# picoschem.net
KiCad netlist of a schematic drawn in EasyEDA
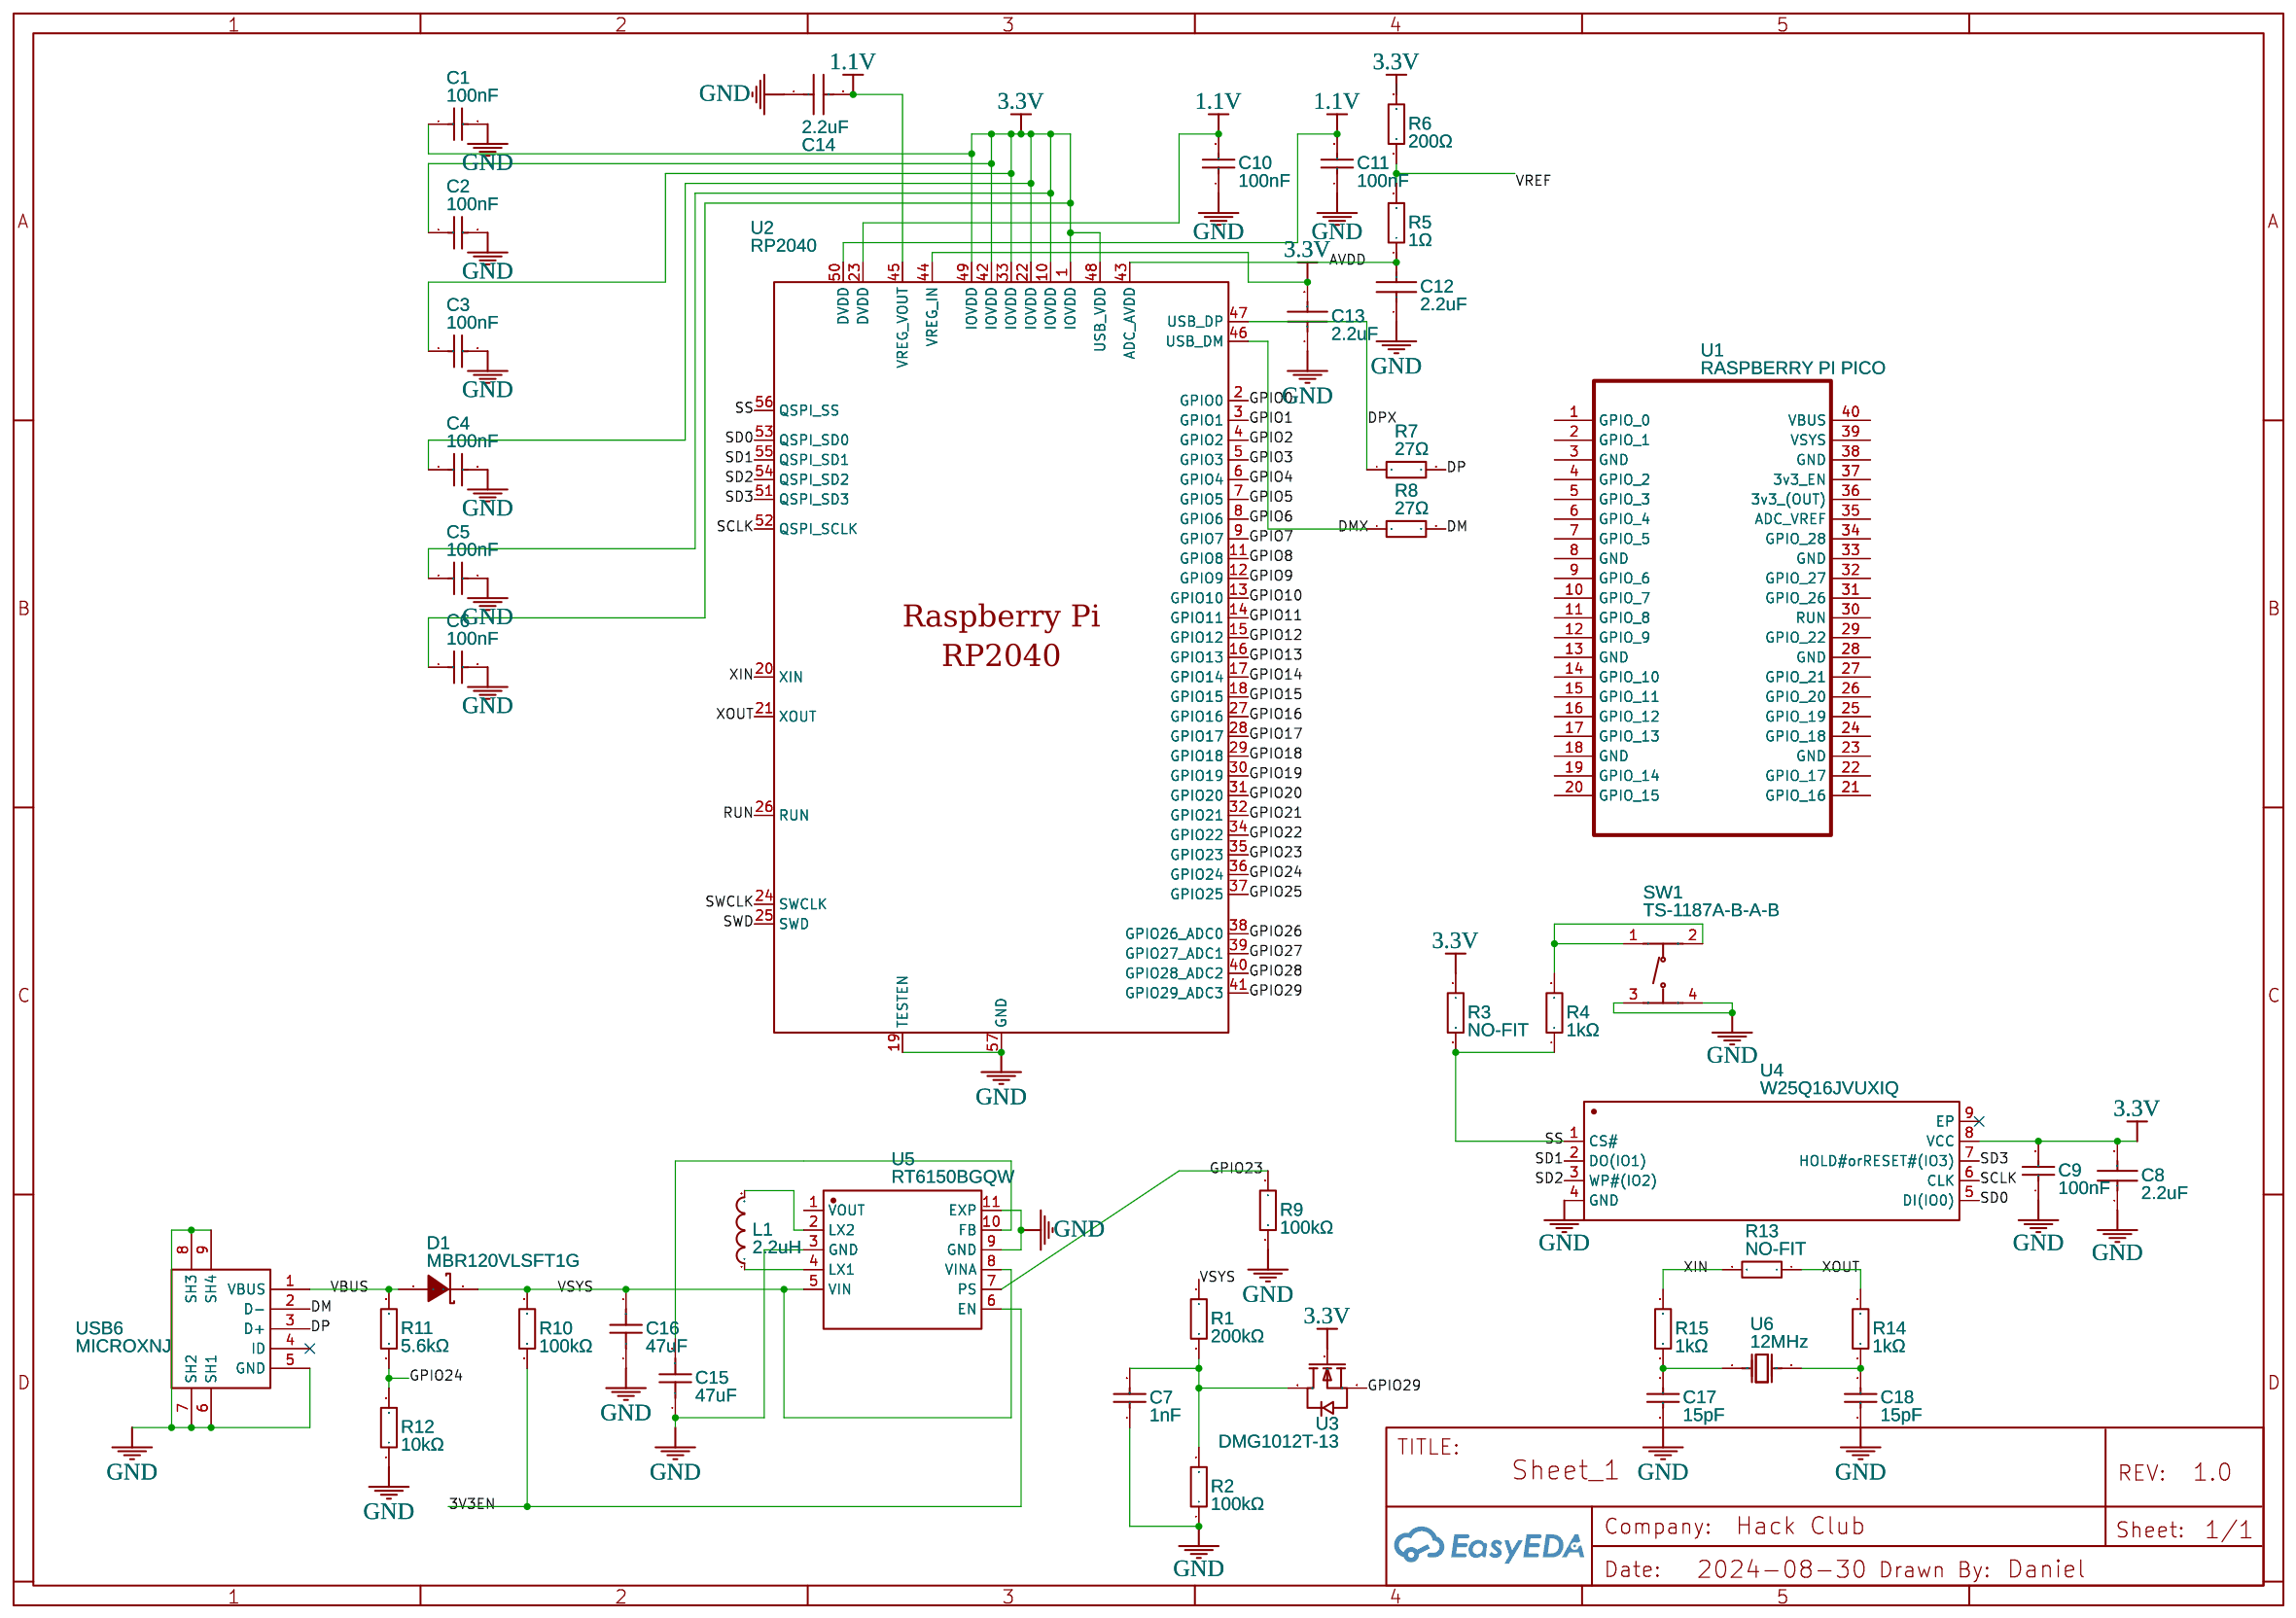
[diagram p0: schematic sheet]

(export (version "E")
  (design (tool "Eeschema 10.0.6"))
  (components
    (comp (ref "C1")
      (value "100nF")
      (fields (field (name "Manufacturer Part") "CGA3E2X7R1H104KT0Y0N") (field (name "Manufacturer") "TDK"))
      (libsource (lib "") (part "CGA3E2X7R1H104KT0Y0N_1"))
    )
    (comp (ref "C2")
      (value "100nF")
      (fields (field (name "Manufacturer Part") "CGA3E2X7R1H104KT0Y0N") (field (name "Manufacturer") "TDK"))
      (libsource (lib "") (part "CGA3E2X7R1H104KT0Y0N_1"))
    )
    (comp (ref "C3")
      (value "100nF")
      (fields (field (name "Manufacturer Part") "CGA3E2X7R1H104KT0Y0N") (field (name "Manufacturer") "TDK"))
      (libsource (lib "") (part "CGA3E2X7R1H104KT0Y0N_1"))
    )
    (comp (ref "C4")
      (value "100nF")
      (fields (field (name "Manufacturer Part") "CGA3E2X7R1H104KT0Y0N") (field (name "Manufacturer") "TDK"))
      (libsource (lib "") (part "CGA3E2X7R1H104KT0Y0N_1"))
    )
    (comp (ref "C5")
      (value "100nF")
      (fields (field (name "Manufacturer Part") "CGA3E2X7R1H104KT0Y0N") (field (name "Manufacturer") "TDK"))
      (libsource (lib "") (part "CGA3E2X7R1H104KT0Y0N_1"))
    )
    (comp (ref "C6")
      (value "100nF")
      (fields (field (name "Manufacturer Part") "CGA3E2X7R1H104KT0Y0N") (field (name "Manufacturer") "TDK"))
      (libsource (lib "") (part "CGA3E2X7R1H104KT0Y0N_1"))
    )
    (comp (ref "C7")
      (value "1nF")
      (fields (field (name "Manufacturer Part") "0805CG102J500NT") (field (name "Manufacturer") "FH(风华)"))
      (libsource (lib "") (part "0805CG102J500NT"))
    )
    (comp (ref "C8")
      (value "2.2uF")
      (fields
        (field (name "Manufacturer Part") "CL05A225MQ5NSNC")
        (field (name "Manufacturer") "SAMSUNG(三星)")
      )
      (libsource (lib "") (part "CL05A225MQ5NSNC_1"))
    )
    (comp (ref "C9")
      (value "100nF")
      (fields (field (name "Manufacturer Part") "CGA3E2X7R1H104KT0Y0N") (field (name "Manufacturer") "TDK"))
      (libsource (lib "") (part "CGA3E2X7R1H104KT0Y0N"))
    )
    (comp (ref "C10")
      (value "100nF")
      (fields (field (name "Manufacturer Part") "CGA3E2X7R1H104KT0Y0N") (field (name "Manufacturer") "TDK"))
      (libsource (lib "") (part "CGA3E2X7R1H104KT0Y0N"))
    )
    (comp (ref "C11")
      (value "100nF")
      (fields (field (name "Manufacturer Part") "CGA3E2X7R1H104KT0Y0N") (field (name "Manufacturer") "TDK"))
      (libsource (lib "") (part "CGA3E2X7R1H104KT0Y0N"))
    )
    (comp (ref "C12")
      (value "2.2uF")
      (fields
        (field (name "Manufacturer Part") "CL05A225MQ5NSNC")
        (field (name "Manufacturer") "SAMSUNG(三星)")
      )
      (libsource (lib "") (part "CL05A225MQ5NSNC_1"))
    )
    (comp (ref "C13")
      (value "2.2uF")
      (fields
        (field (name "Manufacturer Part") "CL05A225MQ5NSNC")
        (field (name "Manufacturer") "SAMSUNG(三星)")
      )
      (libsource (lib "") (part "CL05A225MQ5NSNC_1"))
    )
    (comp (ref "C14")
      (value "2.2uF")
      (fields
        (field (name "Manufacturer Part") "CL05A225MQ5NSNC")
        (field (name "Manufacturer") "SAMSUNG(三星)")
      )
      (libsource (lib "") (part "CL05A225MQ5NSNC"))
    )
    (comp (ref "C15")
      (value "47uF")
      (fields
        (field (name "Manufacturer Part") "CGA0805X5R476M100MT")
        (field (name "Manufacturer") "HRE(芯声)")
      )
      (libsource (lib "") (part "CGA0805X5R476M100MT"))
    )
    (comp (ref "C16")
      (value "47uF")
      (fields
        (field (name "Manufacturer Part") "CGA0805X5R476M100MT")
        (field (name "Manufacturer") "HRE(芯声)")
      )
      (libsource (lib "") (part "CGA0805X5R476M100MT"))
    )
    (comp (ref "C17")
      (value "15pF")
      (fields
        (field (name "Manufacturer Part") "CC0402JRNPO9BN150")
        (field (name "Manufacturer") "YAGEO(国巨)")
      )
      (libsource (lib "") (part "CC0402JRNPO9BN150"))
    )
    (comp (ref "C18")
      (value "15pF")
      (fields
        (field (name "Manufacturer Part") "CC0402JRNPO9BN150")
        (field (name "Manufacturer") "YAGEO(国巨)")
      )
      (libsource (lib "") (part "CC0402JRNPO9BN150"))
    )
    (comp (ref "D1")
      (value "MBR120VLSFT1G")
      (fields (field (name "Manufacturer") "onsemi(安森美)"))
      (libsource (lib "") (part "MBR120VLSFT1G"))
    )
    (comp (ref "L1")
      (value "2.2uH")
      (fields (field (name "Manufacturer Part") "CMI201209U2R2KT") (field (name "Manufacturer") "FH(风华)"))
      (libsource (lib "") (part "CMI201209U2R2KT"))
    )
    (comp (ref "R1")
      (value "200kΩ")
      (fields
        (field (name "Manufacturer Part") "0603WAF2003T5E")
        (field (name "Manufacturer") "UNI-ROYAL(厚声)")
      )
      (libsource (lib "") (part "0603WAF2003T5E"))
    )
    (comp (ref "R2")
      (value "100kΩ")
      (fields
        (field (name "Manufacturer Part") "0603WAF1003T5E")
        (field (name "Manufacturer") "UNI-ROYAL(厚声)")
      )
      (libsource (lib "") (part "0603WAF1003T5E"))
    )
    (comp (ref "R3")
      (value "NO-FIT")
      (fields
        (field (name "Manufacturer Part") "0603WAF2003T5E")
        (field (name "Manufacturer") "UNI-ROYAL(厚声)")
      )
      (libsource (lib "") (part "0603WAF2003T5E"))
    )
    (comp (ref "R4")
      (value "1kΩ")
      (fields
        (field (name "Manufacturer Part") "0603WAF1001T5E")
        (field (name "Manufacturer") "UNI-ROYAL(厚声)")
      )
      (libsource (lib "") (part "0603WAF1001T5E_1"))
    )
    (comp (ref "R5")
      (value "1Ω")
      (fields
        (field (name "Manufacturer Part") "0805W8F100KT5E")
        (field (name "Manufacturer") "UNI-ROYAL(厚声)")
      )
      (libsource (lib "") (part "0805W8F100KT5E"))
    )
    (comp (ref "R6")
      (value "200Ω")
      (fields
        (field (name "Manufacturer Part") "0603WAF2000T5E")
        (field (name "Manufacturer") "UNI-ROYAL(厚声)")
      )
      (libsource (lib "") (part "0603WAF2000T5E"))
    )
    (comp (ref "R7")
      (value "27Ω")
      (fields
        (field (name "Manufacturer Part") "0603WAF270JT5E")
        (field (name "Manufacturer") "UNI-ROYAL(厚声)")
      )
      (libsource (lib "") (part "0603WAF270JT5E"))
    )
    (comp (ref "R8")
      (value "27Ω")
      (fields
        (field (name "Manufacturer Part") "0603WAF270JT5E")
        (field (name "Manufacturer") "UNI-ROYAL(厚声)")
      )
      (libsource (lib "") (part "0603WAF270JT5E"))
    )
    (comp (ref "R9")
      (value "100kΩ")
      (fields
        (field (name "Manufacturer Part") "0603WAF1003T5E")
        (field (name "Manufacturer") "UNI-ROYAL(厚声)")
      )
      (libsource (lib "") (part "0603WAF1003T5E"))
    )
    (comp (ref "R10")
      (value "100kΩ")
      (fields
        (field (name "Manufacturer Part") "0603WAF1003T5E")
        (field (name "Manufacturer") "UNI-ROYAL(厚声)")
      )
      (libsource (lib "") (part "0603WAF1003T5E"))
    )
    (comp (ref "R11")
      (value "5.6kΩ")
      (fields (field (name "Manufacturer Part") "RM10FTN5601") (field (name "Manufacturer") "大毅科技"))
      (libsource (lib "") (part "RM10FTN5601"))
    )
    (comp (ref "R12")
      (value "10kΩ")
      (fields
        (field (name "Manufacturer Part") "0603WAF1002T5E")
        (field (name "Manufacturer") "UNI-ROYAL(厚声)")
      )
      (libsource (lib "") (part "0603WAF1002T5E"))
    )
    (comp (ref "R13")
      (value "NO-FIT")
      (fields
        (field (name "Manufacturer Part") "0603WAF1001T5E")
        (field (name "Manufacturer") "UNI-ROYAL(厚声)")
      )
      (libsource (lib "") (part "0603WAF1001T5E"))
    )
    (comp (ref "R14")
      (value "1kΩ")
      (fields
        (field (name "Manufacturer Part") "0603WAF1001T5E")
        (field (name "Manufacturer") "UNI-ROYAL(厚声)")
      )
      (libsource (lib "") (part "0603WAF1001T5E_1"))
    )
    (comp (ref "R15")
      (value "1kΩ")
      (fields
        (field (name "Manufacturer Part") "0603WAF1001T5E")
        (field (name "Manufacturer") "UNI-ROYAL(厚声)")
      )
      (libsource (lib "") (part "0603WAF1001T5E_1"))
    )
    (comp (ref "SW1")
      (value "TS-1187A-B-A-B")
      (fields (field (name "Manufacturer") "XKB Connectivity(中国星坤)"))
      (libsource (lib "") (part "TS-1187A-B-A-B"))
    )
    (comp (ref "U1") (value "RASPBERRY PI PICO") (libsource (lib "") (part "RASPBERRY PI PICO")))
    (comp (ref "U2")
      (value "RP2040")
      (fields (field (name "Manufacturer") "Raspberry Pi(树莓派)"))
      (libsource (lib "") (part "RP2040"))
    )
    (comp (ref "U3")
      (value "DMG1012T-13")
      (fields (field (name "Manufacturer") "DIODES(美台)"))
      (libsource (lib "") (part "DMG1012T-13"))
    )
    (comp (ref "U4")
      (value "W25Q16JVUXIQ")
      (fields (field (name "Manufacturer") "WINBOND(华邦)"))
      (libsource (lib "") (part "W25Q16JVUXIQ"))
    )
    (comp (ref "U5")
      (value "RT6150BGQW")
      (fields (field (name "Manufacturer") "RICHTEK(立锜)"))
      (libsource (lib "") (part "RT6150BGQW"))
    )
    (comp (ref "U6")
      (value "12MHz")
      (fields
        (field (name "Manufacturer Part") "ABLS-12.000MHZ-B4-T")
        (field (name "Manufacturer") "ABRACON")
      )
      (libsource (lib "") (part "ABLS-12.000MHZ-B4-T"))
    )
    (comp (ref "USB6")
      (value "MICROXNJ")
      (fields (field (name "Manufacturer Part") "MicroXNJ") (field (name "Manufacturer") "SHOU HAN(首韩)"))
      (libsource (lib "") (part "MICROXNJ"))
    )
  )
  (nets
    (net (code "1") (name "/3V3EN") (class "Default")
      (node (ref "R10") (pin "1") (pinfunction "1_1") (pintype "input"))
      (node (ref "U5") (pin "6") (pinfunction "EN_6") (pintype "unspecified"))
    )
    (net (code "2") (name "/AVDD") (class "Default")
      (node (ref "C12") (pin "2") (pinfunction "2_2") (pintype "unspecified"))
      (node (ref "R5") (pin "1") (pinfunction "1_1") (pintype "input"))
      (node (ref "U2") (pin "43") (pinfunction "ADC_AVDD_43") (pintype "bidirectional"))
    )
    (net (code "3") (name "/DM") (class "Default")
      (node (ref "R8") (pin "2") (pinfunction "2_2") (pintype "input"))
      (node (ref "USB6") (pin "2") (pinfunction "D-_2") (pintype "unspecified"))
    )
    (net (code "4") (name "/DMX") (class "Default")
      (node (ref "R8") (pin "1") (pinfunction "1_1") (pintype "input"))
      (node (ref "U2") (pin "46") (pinfunction "USB_DM_46") (pintype "bidirectional"))
    )
    (net (code "5") (name "/DP") (class "Default")
      (node (ref "R7") (pin "2") (pinfunction "2_2") (pintype "input"))
      (node (ref "USB6") (pin "3") (pinfunction "D+_3") (pintype "unspecified"))
    )
    (net (code "6") (name "/DPX") (class "Default")
      (node (ref "R7") (pin "1") (pinfunction "1_1") (pintype "input"))
      (node (ref "U2") (pin "47") (pinfunction "USB_DP_47") (pintype "bidirectional"))
    )
    (net (code "7") (name "/GPIO0") (class "Default")
      (node (ref "U2") (pin "2") (pinfunction "GPIO0_2") (pintype "bidirectional"))
    )
    (net (code "8") (name "/GPIO1") (class "Default")
      (node (ref "U2") (pin "3") (pinfunction "GPIO1_3") (pintype "bidirectional"))
    )
    (net (code "9") (name "/GPIO2") (class "Default")
      (node (ref "U2") (pin "4") (pinfunction "GPIO2_4") (pintype "bidirectional"))
    )
    (net (code "10") (name "/GPIO3") (class "Default")
      (node (ref "U2") (pin "5") (pinfunction "GPIO3_5") (pintype "bidirectional"))
    )
    (net (code "11") (name "/GPIO4") (class "Default")
      (node (ref "U2") (pin "6") (pinfunction "GPIO4_6") (pintype "bidirectional"))
    )
    (net (code "12") (name "/GPIO5") (class "Default")
      (node (ref "U2") (pin "7") (pinfunction "GPIO5_7") (pintype "bidirectional"))
    )
    (net (code "13") (name "/GPIO6") (class "Default")
      (node (ref "U2") (pin "8") (pinfunction "GPIO6_8") (pintype "bidirectional"))
    )
    (net (code "14") (name "/GPIO7") (class "Default")
      (node (ref "U2") (pin "9") (pinfunction "GPIO7_9") (pintype "bidirectional"))
    )
    (net (code "15") (name "/GPIO8") (class "Default")
      (node (ref "U2") (pin "11") (pinfunction "GPIO8_11") (pintype "bidirectional"))
    )
    (net (code "16") (name "/GPIO9") (class "Default")
      (node (ref "U2") (pin "12") (pinfunction "GPIO9_12") (pintype "bidirectional"))
    )
    (net (code "17") (name "/GPIO10") (class "Default")
      (node (ref "U2") (pin "13") (pinfunction "GPIO10_13") (pintype "bidirectional"))
    )
    (net (code "18") (name "/GPIO11") (class "Default")
      (node (ref "U2") (pin "14") (pinfunction "GPIO11_14") (pintype "bidirectional"))
    )
    (net (code "19") (name "/GPIO12") (class "Default")
      (node (ref "U2") (pin "15") (pinfunction "GPIO12_15") (pintype "bidirectional"))
    )
    (net (code "20") (name "/GPIO13") (class "Default")
      (node (ref "U2") (pin "16") (pinfunction "GPIO13_16") (pintype "bidirectional"))
    )
    (net (code "21") (name "/GPIO14") (class "Default")
      (node (ref "U2") (pin "17") (pinfunction "GPIO14_17") (pintype "bidirectional"))
    )
    (net (code "22") (name "/GPIO15") (class "Default")
      (node (ref "U2") (pin "18") (pinfunction "GPIO15_18") (pintype "bidirectional"))
    )
    (net (code "23") (name "/GPIO16") (class "Default")
      (node (ref "U2") (pin "27") (pinfunction "GPIO16_27") (pintype "bidirectional"))
    )
    (net (code "24") (name "/GPIO17") (class "Default")
      (node (ref "U2") (pin "28") (pinfunction "GPIO17_28") (pintype "bidirectional"))
    )
    (net (code "25") (name "/GPIO18") (class "Default")
      (node (ref "U2") (pin "29") (pinfunction "GPIO18_29") (pintype "bidirectional"))
    )
    (net (code "26") (name "/GPIO19") (class "Default")
      (node (ref "U2") (pin "30") (pinfunction "GPIO19_30") (pintype "bidirectional"))
    )
    (net (code "27") (name "/GPIO20") (class "Default")
      (node (ref "U2") (pin "31") (pinfunction "GPIO20_31") (pintype "bidirectional"))
    )
    (net (code "28") (name "/GPIO21") (class "Default")
      (node (ref "U2") (pin "32") (pinfunction "GPIO21_32") (pintype "bidirectional"))
    )
    (net (code "29") (name "/GPIO22") (class "Default")
      (node (ref "U2") (pin "34") (pinfunction "GPIO22_34") (pintype "bidirectional"))
    )
    (net (code "30") (name "/GPIO23") (class "Default")
      (node (ref "R9") (pin "2") (pinfunction "2_2") (pintype "input"))
      (node (ref "U2") (pin "35") (pinfunction "GPIO23_35") (pintype "bidirectional"))
      (node (ref "U5") (pin "7") (pinfunction "PS_7") (pintype "unspecified"))
    )
    (net (code "31") (name "/GPIO24") (class "Default")
      (node (ref "R11") (pin "1") (pinfunction "1_1") (pintype "unspecified"))
      (node (ref "R12") (pin "2") (pinfunction "2_2") (pintype "input"))
      (node (ref "U2") (pin "36") (pinfunction "GPIO24_36") (pintype "bidirectional"))
    )
    (net (code "32") (name "/GPIO25") (class "Default")
      (node (ref "U2") (pin "37") (pinfunction "GPIO25_37") (pintype "bidirectional"))
    )
    (net (code "33") (name "/GPIO26") (class "Default")
      (node (ref "U2") (pin "38") (pinfunction "GPIO26_ADC0_38") (pintype "bidirectional"))
    )
    (net (code "34") (name "/GPIO27") (class "Default")
      (node (ref "U2") (pin "39") (pinfunction "GPIO27_ADC1_39") (pintype "bidirectional"))
    )
    (net (code "35") (name "/GPIO28") (class "Default")
      (node (ref "U2") (pin "40") (pinfunction "GPIO28_ADC2_40") (pintype "bidirectional"))
    )
    (net (code "36") (name "/GPIO29") (class "Default")
      (node (ref "U2") (pin "41") (pinfunction "GPIO29_ADC3_41") (pintype "bidirectional"))
      (node (ref "U3") (pin "2") (pinfunction "S_2") (pintype "unspecified"))
    )
    (net (code "37") (name "/RUN") (class "Default")
      (node (ref "U2") (pin "26") (pinfunction "RUN_26") (pintype "input"))
    )
    (net (code "38") (name "/SCLK") (class "Default")
      (node (ref "U2") (pin "52") (pinfunction "QSPI_SCLK_52") (pintype "output"))
      (node (ref "U4") (pin "6") (pinfunction "CLK_6") (pintype "unspecified"))
    )
    (net (code "39") (name "/SD0") (class "Default")
      (node (ref "U2") (pin "53") (pinfunction "QSPI_SD0_53") (pintype "bidirectional"))
      (node (ref "U4") (pin "5") (pinfunction "DI(IO0)_5") (pintype "unspecified"))
    )
    (net (code "40") (name "/SD1") (class "Default")
      (node (ref "U2") (pin "55") (pinfunction "QSPI_SD1_55") (pintype "bidirectional"))
      (node (ref "U4") (pin "2") (pinfunction "DO(IO1)_2") (pintype "unspecified"))
    )
    (net (code "41") (name "/SD2") (class "Default")
      (node (ref "U2") (pin "54") (pinfunction "QSPI_SD2_54") (pintype "bidirectional"))
      (node (ref "U4") (pin "3") (pinfunction "WP#(IO2)_3") (pintype "unspecified"))
    )
    (net (code "42") (name "/SD3") (class "Default")
      (node (ref "U2") (pin "51") (pinfunction "QSPI_SD3_51") (pintype "bidirectional"))
      (node (ref "U4") (pin "7") (pinfunction "HOLD#orRESET#(IO3)_7") (pintype "unspecified"))
    )
    (net (code "43") (name "/SS") (class "Default")
      (node (ref "R3") (pin "2") (pinfunction "2_2") (pintype "input"))
      (node (ref "R4") (pin "1") (pinfunction "1_1") (pintype "input"))
      (node (ref "U2") (pin "56") (pinfunction "QSPI_SS_56") (pintype "bidirectional"))
      (node (ref "U4") (pin "1") (pinfunction "CS#_1") (pintype "unspecified"))
    )
    (net (code "44") (name "/SWCLK") (class "Default")
      (node (ref "U2") (pin "24") (pinfunction "SWCLK_24") (pintype "output"))
    )
    (net (code "45") (name "/SWD") (class "Default")
      (node (ref "U2") (pin "25") (pinfunction "SWD_25") (pintype "bidirectional"))
    )
    (net (code "46") (name "/VBUS") (class "Default")
      (node (ref "D1") (pin "2") (pinfunction "A_2") (pintype "unspecified"))
      (node (ref "R11") (pin "2") (pinfunction "2_2") (pintype "unspecified"))
      (node (ref "USB6") (pin "1") (pinfunction "VBUS_1") (pintype "unspecified"))
    )
    (net (code "48") (name "/VSYS") (class "Default")
      (node (ref "C16") (pin "2") (pinfunction "2_2") (pintype "unspecified"))
      (node (ref "D1") (pin "1") (pinfunction "K_1") (pintype "unspecified"))
      (node (ref "R1") (pin "1") (pinfunction "1_1") (pintype "input"))
      (node (ref "R10") (pin "2") (pinfunction "2_2") (pintype "input"))
      (node (ref "U5") (pin "5") (pinfunction "VIN_5") (pintype "unspecified"))
      (node (ref "U5") (pin "8") (pinfunction "VINA_8") (pintype "unspecified"))
    )
    (net (code "49") (name "/XIN") (class "Default")
      (node (ref "R13") (pin "2") (pinfunction "2_2") (pintype "input"))
      (node (ref "R15") (pin "2") (pinfunction "2_2") (pintype "input"))
      (node (ref "U2") (pin "20") (pinfunction "XIN_20") (pintype "input"))
    )
    (net (code "50") (name "/XOUT") (class "Default")
      (node (ref "R13") (pin "1") (pinfunction "1_1") (pintype "input"))
      (node (ref "R14") (pin "2") (pinfunction "2_2") (pintype "input"))
      (node (ref "U2") (pin "21") (pinfunction "XOUT_21") (pintype "unspecified"))
    )
    (net (code "51") (name "1.1V") (class "Default")
      (node (ref "C10") (pin "2") (pinfunction "2_2") (pintype "input"))
      (node (ref "C11") (pin "2") (pinfunction "2_2") (pintype "input"))
      (node (ref "C14") (pin "2") (pinfunction "2_2") (pintype "unspecified"))
      (node (ref "U2") (pin "23") (pinfunction "DVDD_23") (pintype "bidirectional"))
      (node (ref "U2") (pin "45") (pinfunction "VREG_VOUT_45") (pintype "bidirectional"))
      (node (ref "U2") (pin "50") (pinfunction "DVDD_50") (pintype "bidirectional"))
    )
    (net (code "52") (name "3.3V") (class "Default")
      (node (ref "C1") (pin "1") (pinfunction "1_1") (pintype "input"))
      (node (ref "C13") (pin "2") (pinfunction "2_2") (pintype "unspecified"))
      (node (ref "C2") (pin "1") (pinfunction "1_1") (pintype "input"))
      (node (ref "C3") (pin "1") (pinfunction "1_1") (pintype "input"))
      (node (ref "C4") (pin "1") (pinfunction "1_1") (pintype "input"))
      (node (ref "C5") (pin "1") (pinfunction "1_1") (pintype "input"))
      (node (ref "C6") (pin "1") (pinfunction "1_1") (pintype "input"))
      (node (ref "C8") (pin "2") (pinfunction "2_2") (pintype "unspecified"))
      (node (ref "C9") (pin "2") (pinfunction "2_2") (pintype "input"))
      (node (ref "R3") (pin "1") (pinfunction "1_1") (pintype "input"))
      (node (ref "R6") (pin "2") (pinfunction "2_2") (pintype "input"))
      (node (ref "U2") (pin "1") (pinfunction "IOVDD_1") (pintype "bidirectional"))
      (node (ref "U2") (pin "10") (pinfunction "IOVDD_10") (pintype "bidirectional"))
      (node (ref "U2") (pin "22") (pinfunction "IOVDD_22") (pintype "bidirectional"))
      (node (ref "U2") (pin "33") (pinfunction "IOVDD_33") (pintype "bidirectional"))
      (node (ref "U2") (pin "42") (pinfunction "IOVDD_42") (pintype "bidirectional"))
      (node (ref "U2") (pin "44") (pinfunction "VREG_IN_44") (pintype "bidirectional"))
      (node (ref "U2") (pin "48") (pinfunction "USB_VDD_48") (pintype "bidirectional"))
      (node (ref "U2") (pin "49") (pinfunction "IOVDD_49") (pintype "bidirectional"))
      (node (ref "U3") (pin "1") (pinfunction "G_1") (pintype "unspecified"))
      (node (ref "U4") (pin "8") (pinfunction "VCC_8") (pintype "unspecified"))
    )
    (net (code "53") (name "GND") (class "Default")
      (node (ref "C1") (pin "2") (pinfunction "2_2") (pintype "input"))
      (node (ref "C10") (pin "1") (pinfunction "1_1") (pintype "input"))
      (node (ref "C11") (pin "1") (pinfunction "1_1") (pintype "input"))
      (node (ref "C12") (pin "1") (pinfunction "1_1") (pintype "unspecified"))
      (node (ref "C13") (pin "1") (pinfunction "1_1") (pintype "unspecified"))
      (node (ref "C14") (pin "1") (pinfunction "1_1") (pintype "unspecified"))
      (node (ref "C15") (pin "1") (pinfunction "1_1") (pintype "unspecified"))
      (node (ref "C16") (pin "1") (pinfunction "1_1") (pintype "unspecified"))
      (node (ref "C17") (pin "1") (pinfunction "1_1") (pintype "input"))
      (node (ref "C18") (pin "1") (pinfunction "1_1") (pintype "input"))
      (node (ref "C2") (pin "2") (pinfunction "2_2") (pintype "input"))
      (node (ref "C3") (pin "2") (pinfunction "2_2") (pintype "input"))
      (node (ref "C4") (pin "2") (pinfunction "2_2") (pintype "input"))
      (node (ref "C5") (pin "2") (pinfunction "2_2") (pintype "input"))
      (node (ref "C6") (pin "2") (pinfunction "2_2") (pintype "input"))
      (node (ref "C7") (pin "1") (pinfunction "1_1") (pintype "input"))
      (node (ref "C8") (pin "1") (pinfunction "1_1") (pintype "unspecified"))
      (node (ref "C9") (pin "1") (pinfunction "1_1") (pintype "input"))
      (node (ref "R12") (pin "1") (pinfunction "1_1") (pintype "input"))
      (node (ref "R2") (pin "1") (pinfunction "1_1") (pintype "input"))
      (node (ref "R9") (pin "1") (pinfunction "1_1") (pintype "input"))
      (node (ref "SW1") (pin "3") (pinfunction "C_3") (pintype "unspecified"))
      (node (ref "SW1") (pin "4") (pinfunction "D_4") (pintype "unspecified"))
      (node (ref "U2") (pin "19") (pinfunction "TESTEN_19") (pintype "unspecified"))
      (node (ref "U2") (pin "57") (pinfunction "GND_57") (pintype "bidirectional"))
      (node (ref "U4") (pin "4") (pinfunction "GND_4") (pintype "unspecified"))
      (node (ref "U5") (pin "11") (pinfunction "EXP_11") (pintype "unspecified"))
      (node (ref "U5") (pin "3") (pinfunction "GND_3") (pintype "unspecified"))
      (node (ref "U5") (pin "9") (pinfunction "GND_9") (pintype "unspecified"))
      (node (ref "USB6") (pin "5") (pinfunction "GND_5") (pintype "unspecified"))
      (node (ref "USB6") (pin "6") (pinfunction "SH1_6") (pintype "unspecified"))
      (node (ref "USB6") (pin "7") (pinfunction "SH2_7") (pintype "unspecified"))
      (node (ref "USB6") (pin "8") (pinfunction "SH3_8") (pintype "unspecified"))
      (node (ref "USB6") (pin "9") (pinfunction "SH4_9") (pintype "unspecified"))
    )
    (net (code "54") (name "Net-(R5-Pad2)") (class "Default")
      (node (ref "R5") (pin "2") (pinfunction "2_2") (pintype "input"))
      (node (ref "R6") (pin "1") (pinfunction "1_1") (pintype "input"))
    )
    (net (code "55") (name "Net-(SW1-A)") (class "Default")
      (node (ref "R4") (pin "2") (pinfunction "2_2") (pintype "input"))
      (node (ref "SW1") (pin "1") (pinfunction "A_1") (pintype "unspecified"))
      (node (ref "SW1") (pin "2") (pinfunction "B_2") (pintype "unspecified"))
    )
    (net (code "56") (name "Net-(U3-D)") (class "Default")
      (node (ref "C7") (pin "2") (pinfunction "2_2") (pintype "input"))
      (node (ref "R1") (pin "2") (pinfunction "2_2") (pintype "input"))
      (node (ref "R2") (pin "2") (pinfunction "2_2") (pintype "input"))
      (node (ref "U3") (pin "3") (pinfunction "D_3") (pintype "unspecified"))
    )
    (net (code "57") (name "Net-(U5-FB)") (class "Default")
      (node (ref "C15") (pin "2") (pinfunction "2_2") (pintype "unspecified"))
      (node (ref "U5") (pin "10") (pinfunction "FB_10") (pintype "unspecified"))
    )
    (net (code "58") (name "Net-(U5-LX1)") (class "Default")
      (node (ref "L1") (pin "1") (pinfunction "1_1") (pintype "unspecified"))
      (node (ref "U5") (pin "4") (pinfunction "LX1_4") (pintype "unspecified"))
    )
    (net (code "59") (name "Net-(U5-LX2)") (class "Default")
      (node (ref "L1") (pin "2") (pinfunction "2_2") (pintype "unspecified"))
      (node (ref "U5") (pin "2") (pinfunction "LX2_2") (pintype "unspecified"))
    )
    (net (code "60") (name "Net-(U6-OSC1)") (class "Default")
      (node (ref "C17") (pin "2") (pinfunction "2_2") (pintype "input"))
      (node (ref "R15") (pin "1") (pinfunction "1_1") (pintype "input"))
      (node (ref "U6") (pin "1") (pinfunction "OSC1_1") (pintype "input"))
    )
    (net (code "61") (name "Net-(U6-OSC2)") (class "Default")
      (node (ref "C18") (pin "2") (pinfunction "2_2") (pintype "input"))
      (node (ref "R14") (pin "1") (pinfunction "1_1") (pintype "input"))
      (node (ref "U6") (pin "2") (pinfunction "OSC2_2") (pintype "input"))
    )
    (net (code "62") (name "unconnected-(U1-3v3_(OUT)-Pad36)") (class "Default")
      (node (ref "U1") (pin "36") (pinfunction "3v3_(OUT)_36") (pintype "unspecified"))
    )
    (net (code "63") (name "unconnected-(U1-3v3_EN-Pad37)") (class "Default")
      (node (ref "U1") (pin "37") (pinfunction "3v3_EN_37") (pintype "unspecified"))
    )
    (net (code "64") (name "unconnected-(U1-ADC_VREF-Pad35)") (class "Default")
      (node (ref "U1") (pin "35") (pinfunction "ADC_VREF_35") (pintype "unspecified"))
    )
    (net (code "65") (name "unconnected-(U1-GND-Pad3)") (class "Default")
      (node (ref "U1") (pin "3") (pinfunction "GND_3") (pintype "unspecified"))
    )
    (net (code "66") (name "unconnected-(U1-GND-Pad8)") (class "Default")
      (node (ref "U1") (pin "8") (pinfunction "GND_8") (pintype "unspecified"))
    )
    (net (code "67") (name "unconnected-(U1-GND-Pad13)") (class "Default")
      (node (ref "U1") (pin "13") (pinfunction "GND_13") (pintype "unspecified"))
    )
    (net (code "68") (name "unconnected-(U1-GND-Pad18)") (class "Default")
      (node (ref "U1") (pin "18") (pinfunction "GND_18") (pintype "unspecified"))
    )
    (net (code "69") (name "unconnected-(U1-GND-Pad23)") (class "Default")
      (node (ref "U1") (pin "23") (pinfunction "GND_23") (pintype "unspecified"))
    )
    (net (code "70") (name "unconnected-(U1-GND-Pad28)") (class "Default")
      (node (ref "U1") (pin "28") (pinfunction "GND_28") (pintype "unspecified"))
    )
    (net (code "71") (name "unconnected-(U1-GND-Pad33)") (class "Default")
      (node (ref "U1") (pin "33") (pinfunction "GND_33") (pintype "unspecified"))
    )
    (net (code "72") (name "unconnected-(U1-GND-Pad38)") (class "Default")
      (node (ref "U1") (pin "38") (pinfunction "GND_38") (pintype "unspecified"))
    )
    (net (code "73") (name "unconnected-(U1-GPIO_0-Pad1)") (class "Default")
      (node (ref "U1") (pin "1") (pinfunction "GPIO_0_1") (pintype "unspecified"))
    )
    (net (code "74") (name "unconnected-(U1-GPIO_1-Pad2)") (class "Default")
      (node (ref "U1") (pin "2") (pinfunction "GPIO_1_2") (pintype "unspecified"))
    )
    (net (code "75") (name "unconnected-(U1-GPIO_2-Pad4)") (class "Default")
      (node (ref "U1") (pin "4") (pinfunction "GPIO_2_4") (pintype "unspecified"))
    )
    (net (code "76") (name "unconnected-(U1-GPIO_3-Pad5)") (class "Default")
      (node (ref "U1") (pin "5") (pinfunction "GPIO_3_5") (pintype "unspecified"))
    )
    (net (code "77") (name "unconnected-(U1-GPIO_4-Pad6)") (class "Default")
      (node (ref "U1") (pin "6") (pinfunction "GPIO_4_6") (pintype "unspecified"))
    )
    (net (code "78") (name "unconnected-(U1-GPIO_5-Pad7)") (class "Default")
      (node (ref "U1") (pin "7") (pinfunction "GPIO_5_7") (pintype "unspecified"))
    )
    (net (code "79") (name "unconnected-(U1-GPIO_6-Pad9)") (class "Default")
      (node (ref "U1") (pin "9") (pinfunction "GPIO_6_9") (pintype "unspecified"))
    )
    (net (code "80") (name "unconnected-(U1-GPIO_7-Pad10)") (class "Default")
      (node (ref "U1") (pin "10") (pinfunction "GPIO_7_10") (pintype "unspecified"))
    )
    (net (code "81") (name "unconnected-(U1-GPIO_8-Pad11)") (class "Default")
      (node (ref "U1") (pin "11") (pinfunction "GPIO_8_11") (pintype "unspecified"))
    )
    (net (code "82") (name "unconnected-(U1-GPIO_9-Pad12)") (class "Default")
      (node (ref "U1") (pin "12") (pinfunction "GPIO_9_12") (pintype "unspecified"))
    )
    (net (code "83") (name "unconnected-(U1-GPIO_10-Pad14)") (class "Default")
      (node (ref "U1") (pin "14") (pinfunction "GPIO_10_14") (pintype "unspecified"))
    )
    (net (code "84") (name "unconnected-(U1-GPIO_11-Pad15)") (class "Default")
      (node (ref "U1") (pin "15") (pinfunction "GPIO_11_15") (pintype "unspecified"))
    )
    (net (code "85") (name "unconnected-(U1-GPIO_12-Pad16)") (class "Default")
      (node (ref "U1") (pin "16") (pinfunction "GPIO_12_16") (pintype "unspecified"))
    )
    (net (code "86") (name "unconnected-(U1-GPIO_13-Pad17)") (class "Default")
      (node (ref "U1") (pin "17") (pinfunction "GPIO_13_17") (pintype "unspecified"))
    )
    (net (code "87") (name "unconnected-(U1-GPIO_14-Pad19)") (class "Default")
      (node (ref "U1") (pin "19") (pinfunction "GPIO_14_19") (pintype "unspecified"))
    )
    (net (code "88") (name "unconnected-(U1-GPIO_15-Pad20)") (class "Default")
      (node (ref "U1") (pin "20") (pinfunction "GPIO_15_20") (pintype "unspecified"))
    )
    (net (code "89") (name "unconnected-(U1-GPIO_16-Pad21)") (class "Default")
      (node (ref "U1") (pin "21") (pinfunction "GPIO_16_21") (pintype "unspecified"))
    )
    (net (code "90") (name "unconnected-(U1-GPIO_17-Pad22)") (class "Default")
      (node (ref "U1") (pin "22") (pinfunction "GPIO_17_22") (pintype "unspecified"))
    )
    (net (code "91") (name "unconnected-(U1-GPIO_18-Pad24)") (class "Default")
      (node (ref "U1") (pin "24") (pinfunction "GPIO_18_24") (pintype "unspecified"))
    )
    (net (code "92") (name "unconnected-(U1-GPIO_19-Pad25)") (class "Default")
      (node (ref "U1") (pin "25") (pinfunction "GPIO_19_25") (pintype "unspecified"))
    )
    (net (code "93") (name "unconnected-(U1-GPIO_20-Pad26)") (class "Default")
      (node (ref "U1") (pin "26") (pinfunction "GPIO_20_26") (pintype "unspecified"))
    )
    (net (code "94") (name "unconnected-(U1-GPIO_21-Pad27)") (class "Default")
      (node (ref "U1") (pin "27") (pinfunction "GPIO_21_27") (pintype "unspecified"))
    )
    (net (code "95") (name "unconnected-(U1-GPIO_22-Pad29)") (class "Default")
      (node (ref "U1") (pin "29") (pinfunction "GPIO_22_29") (pintype "unspecified"))
    )
    (net (code "96") (name "unconnected-(U1-GPIO_26-Pad31)") (class "Default")
      (node (ref "U1") (pin "31") (pinfunction "GPIO_26_31") (pintype "unspecified"))
    )
    (net (code "97") (name "unconnected-(U1-GPIO_27-Pad32)") (class "Default")
      (node (ref "U1") (pin "32") (pinfunction "GPIO_27_32") (pintype "unspecified"))
    )
    (net (code "98") (name "unconnected-(U1-GPIO_28-Pad34)") (class "Default")
      (node (ref "U1") (pin "34") (pinfunction "GPIO_28_34") (pintype "unspecified"))
    )
    (net (code "99") (name "unconnected-(U1-RUN-Pad30)") (class "Default")
      (node (ref "U1") (pin "30") (pinfunction "RUN_30") (pintype "unspecified"))
    )
    (net (code "100") (name "unconnected-(U1-VBUS-Pad40)") (class "Default")
      (node (ref "U1") (pin "40") (pinfunction "VBUS_40") (pintype "unspecified"))
    )
    (net (code "101") (name "unconnected-(U1-VSYS-Pad39)") (class "Default")
      (node (ref "U1") (pin "39") (pinfunction "VSYS_39") (pintype "unspecified"))
    )
    (net (code "102") (name "unconnected-(U4-EP-Pad9)") (class "Default")
      (node (ref "U4") (pin "9") (pinfunction "EP_9") (pintype "unspecified+no_connect"))
    )
    (net (code "103") (name "unconnected-(U5-VOUT-Pad1)") (class "Default")
      (node (ref "U5") (pin "1") (pinfunction "VOUT_1") (pintype "unspecified"))
    )
    (net (code "104") (name "unconnected-(USB6-ID-Pad4)") (class "Default")
      (node (ref "USB6") (pin "4") (pinfunction "ID_4") (pintype "unspecified+no_connect"))
    )
  )
)
